# INCAM.net
KiCad netlist of a schematic drawn in Altium Designer
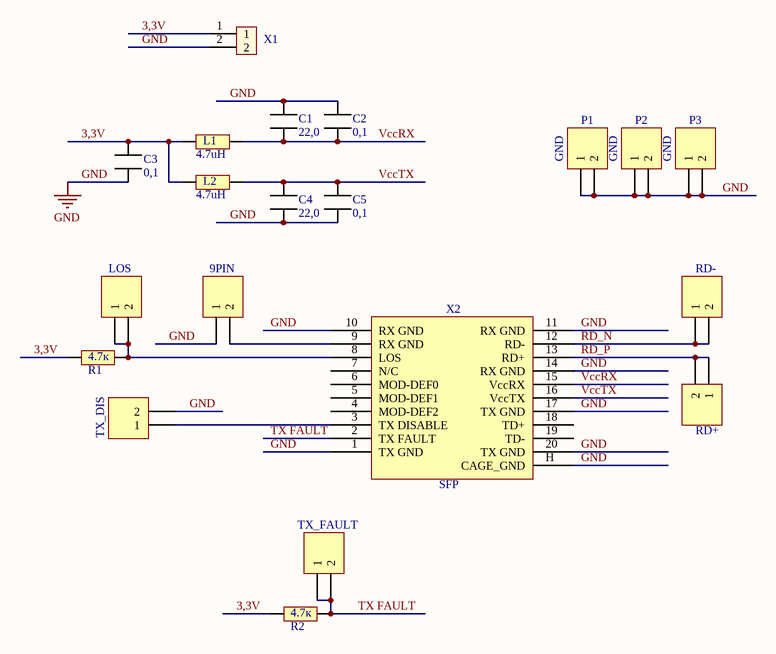
[diagram p0: INCAM.SchDoc]

(export (version "E")
  (design (tool "Eeschema 10.0.6"))
  (components
    (comp (ref "9PIN")
      (value "Header 2")
      (footprint "HDR1X2")
      (description "Header, 2-Pin")
      (fields (field (name "PUBLISHER") "Altium Limited"))
      (libsource (lib "Miscellaneous Connectors") (part "Header 2"))
    )
    (comp (ref "C1") (value "22,0") (footprint "Cap_BIG") (libsource (lib "Schlib") (part "CAP_BIG")))
    (comp (ref "C2") (value "0,1") (footprint "CAP_SMALL") (libsource (lib "Schlib") (part "CAP_SMALL")))
    (comp (ref "C3") (value "0,1") (footprint "CAP_SMALL") (libsource (lib "Schlib") (part "CAP_SMALL")))
    (comp (ref "C4") (value "22,0") (footprint "Cap_BIG") (libsource (lib "Schlib") (part "CAP_BIG")))
    (comp (ref "C5") (value "0,1") (footprint "CAP_SMALL") (libsource (lib "Schlib") (part "CAP_SMALL")))
    (comp (ref "L1") (value "4.7uH") (footprint "RES") (libsource (lib "Schlib") (part "RES")))
    (comp (ref "L2") (value "4.7uH") (footprint "RES") (libsource (lib "Schlib") (part "RES")))
    (comp (ref "LOS")
      (value "Header 2")
      (footprint "HDR1X2")
      (description "Header, 2-Pin")
      (fields (field (name "PUBLISHER") "Altium Limited"))
      (libsource (lib "Miscellaneous Connectors") (part "Header 2"))
    )
    (comp (ref "P1")
      (value "GND")
      (footprint "HDR1X2")
      (description "Header, 2-Pin")
      (fields (field (name "PUBLISHER") "Altium Limited"))
      (libsource (lib "Miscellaneous Connectors") (part "Header 2"))
    )
    (comp (ref "P2")
      (value "GND")
      (footprint "HDR1X2")
      (description "Header, 2-Pin")
      (fields (field (name "PUBLISHER") "Altium Limited"))
      (libsource (lib "Miscellaneous Connectors") (part "Header 2"))
    )
    (comp (ref "P3")
      (value "GND")
      (footprint "HDR1X2")
      (description "Header, 2-Pin")
      (fields (field (name "PUBLISHER") "Altium Limited"))
      (libsource (lib "Miscellaneous Connectors") (part "Header 2"))
    )
    (comp (ref "R1") (value "4.7к") (footprint "RES") (libsource (lib "Schlib") (part "RES")))
    (comp (ref "R2") (value "4.7к") (footprint "RES") (libsource (lib "Schlib") (part "RES")))
    (comp (ref "RD+")
      (value "Header 2")
      (footprint "HDR1X2")
      (description "Header, 2-Pin")
      (fields (field (name "PUBLISHER") "Altium Limited"))
      (libsource (lib "") (part "Header 2_2"))
    )
    (comp (ref "RD-")
      (value "Header 2")
      (footprint "HDR1X2")
      (description "Header, 2-Pin")
      (fields (field (name "PUBLISHER") "Altium Limited"))
      (libsource (lib "Miscellaneous Connectors") (part "Header 2"))
    )
    (comp (ref "TX_DIS")
      (value "Header 2")
      (footprint "HDR1X2")
      (description "Header, 2-Pin")
      (fields (field (name "PUBLISHER") "Altium Limited"))
      (libsource (lib "") (part "Header 2_1"))
    )
    (comp (ref "TX_FAULT")
      (value "Header 2")
      (footprint "HDR1X2")
      (description "Header, 2-Pin")
      (fields (field (name "PUBLISHER") "Altium Limited"))
      (libsource (lib "Miscellaneous Connectors") (part "Header 2"))
    )
    (comp (ref "X1") (value "KL_2") (footprint "KLEMMNIK_2") (libsource (lib "Schlib") (part "KLEMMNIK_2")))
    (comp (ref "X2") (value "SFP") (footprint "SFP-20pin") (libsource (lib "MIT_Schlib") (part "SFP-20pin")))
  )
  (nets
    (net (code "1") (name "/3,3V") (class "Default")
      (node (ref "C3") (pin "2") (pinfunction "2_2") (pintype "passive"))
      (node (ref "L1") (pin "1") (pinfunction "1_1") (pintype "passive"))
      (node (ref "L2") (pin "1") (pinfunction "1_1") (pintype "passive"))
      (node (ref "R1") (pin "1") (pinfunction "1_1") (pintype "passive"))
      (node (ref "R2") (pin "1") (pinfunction "1_1") (pintype "passive"))
      (node (ref "X1") (pin "1") (pinfunction "1_1") (pintype "passive"))
    )
    (net (code "2") (name "/RD_N") (class "Default")
      (node (ref "RD-") (pin "1") (pinfunction "1_1") (pintype "passive"))
      (node (ref "RD-") (pin "2") (pinfunction "2_2") (pintype "passive"))
      (node (ref "X2") (pin "12") (pinfunction "RD-_12") (pintype "passive"))
    )
    (net (code "3") (name "/RD_P") (class "Default")
      (node (ref "RD+") (pin "1") (pinfunction "1_1") (pintype "passive"))
      (node (ref "RD+") (pin "2") (pinfunction "2_2") (pintype "passive"))
      (node (ref "X2") (pin "13") (pinfunction "RD+_13") (pintype "passive"))
    )
    (net (code "4") (name "/TX FAULT") (class "Default")
      (node (ref "R2") (pin "2") (pinfunction "2_2") (pintype "passive"))
      (node (ref "TX_FAULT") (pin "1") (pinfunction "1_1") (pintype "passive"))
      (node (ref "TX_FAULT") (pin "2") (pinfunction "2_2") (pintype "passive"))
      (node (ref "X2") (pin "2") (pinfunction "TX_FAULT_2") (pintype "passive"))
    )
    (net (code "5") (name "/VccRX") (class "Default")
      (node (ref "C1") (pin "1") (pinfunction "1_1") (pintype "passive"))
      (node (ref "C2") (pin "1") (pinfunction "1_1") (pintype "passive"))
      (node (ref "L1") (pin "2") (pinfunction "2_2") (pintype "passive"))
      (node (ref "X2") (pin "15") (pinfunction "VccRX_15") (pintype "passive"))
    )
    (net (code "6") (name "/VccTX") (class "Default")
      (node (ref "C4") (pin "2") (pinfunction "2_2") (pintype "passive"))
      (node (ref "C5") (pin "2") (pinfunction "2_2") (pintype "passive"))
      (node (ref "L2") (pin "2") (pinfunction "2_2") (pintype "passive"))
      (node (ref "X2") (pin "16") (pinfunction "VccTX_16") (pintype "passive"))
    )
    (net (code "7") (name "GND") (class "Default")
      (node (ref "9PIN") (pin "1") (pinfunction "1_1") (pintype "passive"))
      (node (ref "C1") (pin "2") (pinfunction "2_2") (pintype "passive"))
      (node (ref "C2") (pin "2") (pinfunction "2_2") (pintype "passive"))
      (node (ref "C3") (pin "1") (pinfunction "1_1") (pintype "passive"))
      (node (ref "C4") (pin "1") (pinfunction "1_1") (pintype "passive"))
      (node (ref "C5") (pin "1") (pinfunction "1_1") (pintype "passive"))
      (node (ref "P1") (pin "1") (pinfunction "1_1") (pintype "passive"))
      (node (ref "P1") (pin "2") (pinfunction "2_2") (pintype "passive"))
      (node (ref "P2") (pin "1") (pinfunction "1_1") (pintype "passive"))
      (node (ref "P2") (pin "2") (pinfunction "2_2") (pintype "passive"))
      (node (ref "P3") (pin "1") (pinfunction "1_1") (pintype "passive"))
      (node (ref "P3") (pin "2") (pinfunction "2_2") (pintype "passive"))
      (node (ref "TX_DIS") (pin "2") (pinfunction "2_2") (pintype "passive"))
      (node (ref "X1") (pin "2") (pinfunction "2_2") (pintype "passive"))
      (node (ref "X2") (pin "1") (pinfunction "TX_GND_1") (pintype "passive"))
      (node (ref "X2") (pin "10") (pinfunction "RX_GND_10") (pintype "passive"))
      (node (ref "X2") (pin "11") (pinfunction "RX_GND_11") (pintype "passive"))
      (node (ref "X2") (pin "14") (pinfunction "RX_GND_14") (pintype "passive"))
      (node (ref "X2") (pin "17") (pinfunction "TX_GND_17") (pintype "passive"))
      (node (ref "X2") (pin "20") (pinfunction "TX_GND_20") (pintype "passive"))
      (node (ref "X2") (pin "H") (pinfunction "CAGE_GND_H") (pintype "passive"))
    )
    (net (code "8") (name "Net-(9PIN-Pad2)") (class "Default")
      (node (ref "9PIN") (pin "2") (pinfunction "2_2") (pintype "passive"))
      (node (ref "X2") (pin "9") (pinfunction "RX_GND_9") (pintype "passive"))
    )
    (net (code "9") (name "Net-(X2-LOS)") (class "Default")
      (node (ref "LOS") (pin "1") (pinfunction "1_1") (pintype "passive"))
      (node (ref "LOS") (pin "2") (pinfunction "2_2") (pintype "passive"))
      (node (ref "R1") (pin "2") (pinfunction "2_2") (pintype "passive"))
      (node (ref "X2") (pin "8") (pinfunction "LOS_8") (pintype "passive"))
    )
    (net (code "10") (name "Net-(X2-TX_DISABLE)") (class "Default")
      (node (ref "TX_DIS") (pin "1") (pinfunction "1_1") (pintype "passive"))
      (node (ref "X2") (pin "3") (pinfunction "TX_DISABLE_3") (pintype "passive"))
    )
    (net (code "11") (name "unconnected-(X2-MOD-DEF0-Pad6)") (class "Default")
      (node (ref "X2") (pin "6") (pinfunction "MOD-DEF0_6") (pintype "passive"))
    )
    (net (code "12") (name "unconnected-(X2-MOD-DEF1-Pad5)") (class "Default")
      (node (ref "X2") (pin "5") (pinfunction "MOD-DEF1_5") (pintype "passive"))
    )
    (net (code "13") (name "unconnected-(X2-MOD-DEF2-Pad4)") (class "Default")
      (node (ref "X2") (pin "4") (pinfunction "MOD-DEF2_4") (pintype "passive"))
    )
    (net (code "14") (name "unconnected-(X2-N{slash}C-Pad7)") (class "Default")
      (node (ref "X2") (pin "7") (pinfunction "N/C_7") (pintype "passive"))
    )
    (net (code "15") (name "unconnected-(X2-TD+-Pad18)") (class "Default")
      (node (ref "X2") (pin "18") (pinfunction "TD+_18") (pintype "passive"))
    )
    (net (code "16") (name "unconnected-(X2-TD--Pad19)") (class "Default")
      (node (ref "X2") (pin "19") (pinfunction "TD-_19") (pintype "passive"))
    )
  )
)
